# gloBrdB.net
KiCad netlist of a schematic drawn in EAGLE
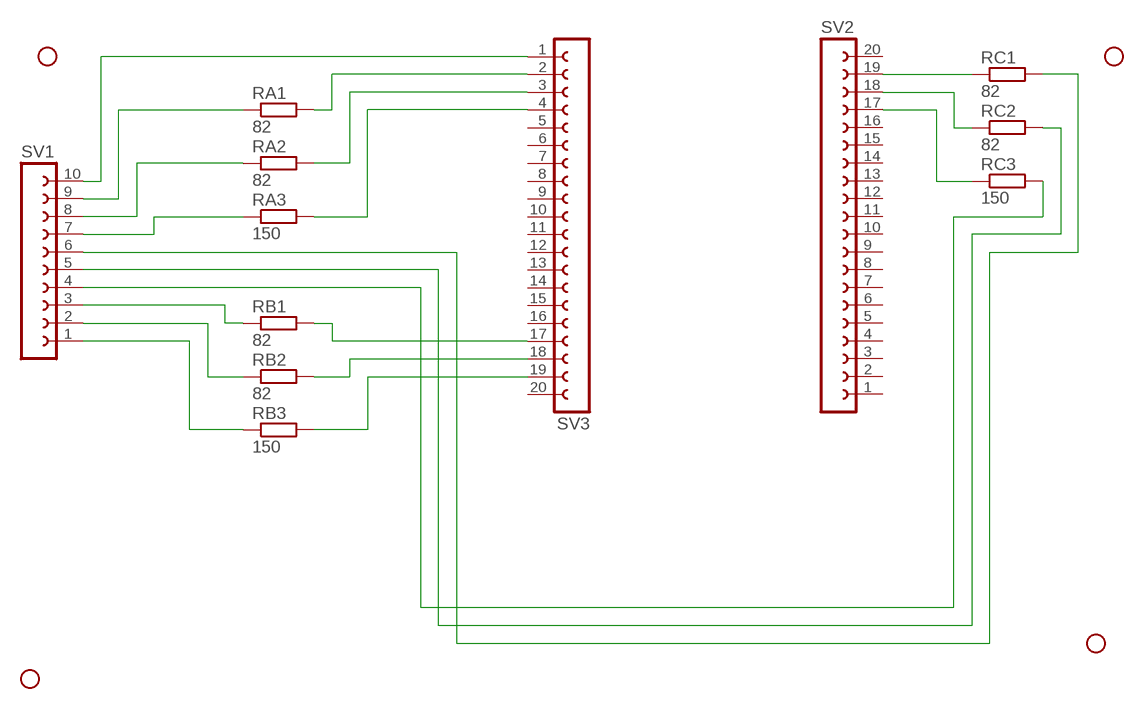
[diagram p0: schematic, sheet 1]

(export (version "E")
  (design (tool "Eeschema 10.0.6"))
  (components
    (comp (ref "RA1")
      (value "82")
      (footprint "eagle-import:0204_7")
      (libsource (lib "eagle-import") (part "R-EU_0204/7"))
    )
    (comp (ref "RA2")
      (value "82")
      (footprint "eagle-import:0204_7")
      (libsource (lib "eagle-import") (part "R-EU_0204/7"))
    )
    (comp (ref "RA3")
      (value "150")
      (footprint "eagle-import:0204_7")
      (libsource (lib "eagle-import") (part "R-EU_0204/7"))
    )
    (comp (ref "RB1")
      (value "82")
      (footprint "eagle-import:0204_7")
      (libsource (lib "eagle-import") (part "R-EU_0204/7"))
    )
    (comp (ref "RB2")
      (value "82")
      (footprint "eagle-import:0204_7")
      (libsource (lib "eagle-import") (part "R-EU_0204/7"))
    )
    (comp (ref "RB3")
      (value "150")
      (footprint "eagle-import:0204_7")
      (libsource (lib "eagle-import") (part "R-EU_0204/7"))
    )
    (comp (ref "RC1")
      (value "82")
      (footprint "eagle-import:0204_7")
      (libsource (lib "eagle-import") (part "R-EU_0204/7"))
    )
    (comp (ref "RC2")
      (value "82")
      (footprint "eagle-import:0204_7")
      (libsource (lib "eagle-import") (part "R-EU_0204/7"))
    )
    (comp (ref "RC3")
      (value "150")
      (footprint "eagle-import:0204_7")
      (libsource (lib "eagle-import") (part "R-EU_0204/7"))
    )
    (comp (ref "STANDOFF1")
      (value "STAND-OFF")
      (footprint "eagle-import:STAND-OFF")
      (libsource (lib "eagle-import") (part "STAND-OFF"))
    )
    (comp (ref "STANDOFF2")
      (value "STAND-OFF")
      (footprint "eagle-import:STAND-OFF")
      (libsource (lib "eagle-import") (part "STAND-OFF"))
    )
    (comp (ref "STANDOFF3")
      (value "STAND-OFF")
      (footprint "eagle-import:STAND-OFF")
      (libsource (lib "eagle-import") (part "STAND-OFF"))
    )
    (comp (ref "STANDOFF4")
      (value "STAND-OFF")
      (footprint "eagle-import:STAND-OFF")
      (libsource (lib "eagle-import") (part "STAND-OFF"))
    )
    (comp (ref "SV1")
      (value "FE10-1")
      (footprint "eagle-import:FE10")
      (libsource (lib "eagle-import") (part "FE10-1"))
    )
    (comp (ref "SV2")
      (value "FE20-1")
      (footprint "eagle-import:FE20")
      (libsource (lib "eagle-import") (part "FE20-1"))
    )
    (comp (ref "SV3")
      (value "FE20-1")
      (footprint "eagle-import:FE20")
      (libsource (lib "eagle-import") (part "FE20-1"))
    )
  )
  (nets
    (net (code "1") (name "Net-(RA1-Pad1)") (class "Default")
      (node (ref "RA1") (pin "1") (pinfunction "1_1") (pintype "passive"))
      (node (ref "SV1") (pin "9") (pinfunction "9_9") (pintype "passive"))
    )
    (net (code "2") (name "Net-(RA1-Pad2)") (class "Default")
      (node (ref "RA1") (pin "2") (pinfunction "2_2") (pintype "passive"))
      (node (ref "SV3") (pin "2") (pinfunction "2_2") (pintype "passive"))
    )
    (net (code "3") (name "Net-(RA2-Pad1)") (class "Default")
      (node (ref "RA2") (pin "1") (pinfunction "1_1") (pintype "passive"))
      (node (ref "SV1") (pin "8") (pinfunction "8_8") (pintype "passive"))
    )
    (net (code "4") (name "Net-(RA2-Pad2)") (class "Default")
      (node (ref "RA2") (pin "2") (pinfunction "2_2") (pintype "passive"))
      (node (ref "SV3") (pin "3") (pinfunction "3_3") (pintype "passive"))
    )
    (net (code "5") (name "Net-(RA3-Pad1)") (class "Default")
      (node (ref "RA3") (pin "1") (pinfunction "1_1") (pintype "passive"))
      (node (ref "SV1") (pin "7") (pinfunction "7_7") (pintype "passive"))
    )
    (net (code "6") (name "Net-(RA3-Pad2)") (class "Default")
      (node (ref "RA3") (pin "2") (pinfunction "2_2") (pintype "passive"))
      (node (ref "SV3") (pin "4") (pinfunction "4_4") (pintype "passive"))
    )
    (net (code "7") (name "Net-(RB1-Pad1)") (class "Default")
      (node (ref "RB1") (pin "1") (pinfunction "1_1") (pintype "passive"))
      (node (ref "SV1") (pin "3") (pinfunction "3_3") (pintype "passive"))
    )
    (net (code "8") (name "Net-(RB1-Pad2)") (class "Default")
      (node (ref "RB1") (pin "2") (pinfunction "2_2") (pintype "passive"))
      (node (ref "SV3") (pin "17") (pinfunction "17_17") (pintype "passive"))
    )
    (net (code "9") (name "Net-(RB2-Pad1)") (class "Default")
      (node (ref "RB2") (pin "1") (pinfunction "1_1") (pintype "passive"))
      (node (ref "SV1") (pin "2") (pinfunction "2_2") (pintype "passive"))
    )
    (net (code "10") (name "Net-(RB2-Pad2)") (class "Default")
      (node (ref "RB2") (pin "2") (pinfunction "2_2") (pintype "passive"))
      (node (ref "SV3") (pin "18") (pinfunction "18_18") (pintype "passive"))
    )
    (net (code "11") (name "Net-(RB3-Pad1)") (class "Default")
      (node (ref "RB3") (pin "1") (pinfunction "1_1") (pintype "passive"))
      (node (ref "SV1") (pin "1") (pinfunction "1_1") (pintype "passive"))
    )
    (net (code "12") (name "Net-(RB3-Pad2)") (class "Default")
      (node (ref "RB3") (pin "2") (pinfunction "2_2") (pintype "passive"))
      (node (ref "SV3") (pin "19") (pinfunction "19_19") (pintype "passive"))
    )
    (net (code "13") (name "Net-(RC1-Pad1)") (class "Default")
      (node (ref "RC1") (pin "1") (pinfunction "1_1") (pintype "passive"))
      (node (ref "SV2") (pin "19") (pinfunction "19_19") (pintype "passive"))
    )
    (net (code "14") (name "Net-(RC1-Pad2)") (class "Default")
      (node (ref "RC1") (pin "2") (pinfunction "2_2") (pintype "passive"))
      (node (ref "SV1") (pin "6") (pinfunction "6_6") (pintype "passive"))
    )
    (net (code "15") (name "Net-(RC2-Pad1)") (class "Default")
      (node (ref "RC2") (pin "1") (pinfunction "1_1") (pintype "passive"))
      (node (ref "SV2") (pin "18") (pinfunction "18_18") (pintype "passive"))
    )
    (net (code "16") (name "Net-(RC2-Pad2)") (class "Default")
      (node (ref "RC2") (pin "2") (pinfunction "2_2") (pintype "passive"))
      (node (ref "SV1") (pin "5") (pinfunction "5_5") (pintype "passive"))
    )
    (net (code "17") (name "Net-(RC3-Pad1)") (class "Default")
      (node (ref "RC3") (pin "1") (pinfunction "1_1") (pintype "passive"))
      (node (ref "SV2") (pin "17") (pinfunction "17_17") (pintype "passive"))
    )
    (net (code "18") (name "Net-(RC3-Pad2)") (class "Default")
      (node (ref "RC3") (pin "2") (pinfunction "2_2") (pintype "passive"))
      (node (ref "SV1") (pin "4") (pinfunction "4_4") (pintype "passive"))
    )
    (net (code "19") (name "Net-(SV1-Pad10)") (class "Default")
      (node (ref "SV1") (pin "10") (pinfunction "10_10") (pintype "passive"))
      (node (ref "SV3") (pin "1") (pinfunction "1_1") (pintype "passive"))
    )
    (net (code "20") (name "unconnected-(SV2-Pad1)") (class "Default")
      (node (ref "SV2") (pin "1") (pinfunction "1_1") (pintype "passive"))
    )
    (net (code "21") (name "unconnected-(SV2-Pad2)") (class "Default")
      (node (ref "SV2") (pin "2") (pinfunction "2_2") (pintype "passive"))
    )
    (net (code "22") (name "unconnected-(SV2-Pad3)") (class "Default")
      (node (ref "SV2") (pin "3") (pinfunction "3_3") (pintype "passive"))
    )
    (net (code "23") (name "unconnected-(SV2-Pad4)") (class "Default")
      (node (ref "SV2") (pin "4") (pinfunction "4_4") (pintype "passive"))
    )
    (net (code "24") (name "unconnected-(SV2-Pad5)") (class "Default")
      (node (ref "SV2") (pin "5") (pinfunction "5_5") (pintype "passive"))
    )
    (net (code "25") (name "unconnected-(SV2-Pad6)") (class "Default")
      (node (ref "SV2") (pin "6") (pinfunction "6_6") (pintype "passive"))
    )
    (net (code "26") (name "unconnected-(SV2-Pad7)") (class "Default")
      (node (ref "SV2") (pin "7") (pinfunction "7_7") (pintype "passive"))
    )
    (net (code "27") (name "unconnected-(SV2-Pad8)") (class "Default")
      (node (ref "SV2") (pin "8") (pinfunction "8_8") (pintype "passive"))
    )
    (net (code "28") (name "unconnected-(SV2-Pad9)") (class "Default")
      (node (ref "SV2") (pin "9") (pinfunction "9_9") (pintype "passive"))
    )
    (net (code "29") (name "unconnected-(SV2-Pad10)") (class "Default")
      (node (ref "SV2") (pin "10") (pinfunction "10_10") (pintype "passive"))
    )
    (net (code "30") (name "unconnected-(SV2-Pad11)") (class "Default")
      (node (ref "SV2") (pin "11") (pinfunction "11_11") (pintype "passive"))
    )
    (net (code "31") (name "unconnected-(SV2-Pad12)") (class "Default")
      (node (ref "SV2") (pin "12") (pinfunction "12_12") (pintype "passive"))
    )
    (net (code "32") (name "unconnected-(SV2-Pad13)") (class "Default")
      (node (ref "SV2") (pin "13") (pinfunction "13_13") (pintype "passive"))
    )
    (net (code "33") (name "unconnected-(SV2-Pad14)") (class "Default")
      (node (ref "SV2") (pin "14") (pinfunction "14_14") (pintype "passive"))
    )
    (net (code "34") (name "unconnected-(SV2-Pad15)") (class "Default")
      (node (ref "SV2") (pin "15") (pinfunction "15_15") (pintype "passive"))
    )
    (net (code "35") (name "unconnected-(SV2-Pad16)") (class "Default")
      (node (ref "SV2") (pin "16") (pinfunction "16_16") (pintype "passive"))
    )
    (net (code "36") (name "unconnected-(SV2-Pad20)") (class "Default")
      (node (ref "SV2") (pin "20") (pinfunction "20_20") (pintype "passive"))
    )
    (net (code "37") (name "unconnected-(SV3-Pad5)") (class "Default")
      (node (ref "SV3") (pin "5") (pinfunction "5_5") (pintype "passive"))
    )
    (net (code "38") (name "unconnected-(SV3-Pad6)") (class "Default")
      (node (ref "SV3") (pin "6") (pinfunction "6_6") (pintype "passive"))
    )
    (net (code "39") (name "unconnected-(SV3-Pad7)") (class "Default")
      (node (ref "SV3") (pin "7") (pinfunction "7_7") (pintype "passive"))
    )
    (net (code "40") (name "unconnected-(SV3-Pad8)") (class "Default")
      (node (ref "SV3") (pin "8") (pinfunction "8_8") (pintype "passive"))
    )
    (net (code "41") (name "unconnected-(SV3-Pad9)") (class "Default")
      (node (ref "SV3") (pin "9") (pinfunction "9_9") (pintype "passive"))
    )
    (net (code "42") (name "unconnected-(SV3-Pad10)") (class "Default")
      (node (ref "SV3") (pin "10") (pinfunction "10_10") (pintype "passive"))
    )
    (net (code "43") (name "unconnected-(SV3-Pad11)") (class "Default")
      (node (ref "SV3") (pin "11") (pinfunction "11_11") (pintype "passive"))
    )
    (net (code "44") (name "unconnected-(SV3-Pad12)") (class "Default")
      (node (ref "SV3") (pin "12") (pinfunction "12_12") (pintype "passive"))
    )
    (net (code "45") (name "unconnected-(SV3-Pad13)") (class "Default")
      (node (ref "SV3") (pin "13") (pinfunction "13_13") (pintype "passive"))
    )
    (net (code "46") (name "unconnected-(SV3-Pad14)") (class "Default")
      (node (ref "SV3") (pin "14") (pinfunction "14_14") (pintype "passive"))
    )
    (net (code "47") (name "unconnected-(SV3-Pad15)") (class "Default")
      (node (ref "SV3") (pin "15") (pinfunction "15_15") (pintype "passive"))
    )
    (net (code "48") (name "unconnected-(SV3-Pad16)") (class "Default")
      (node (ref "SV3") (pin "16") (pinfunction "16_16") (pintype "passive"))
    )
    (net (code "49") (name "unconnected-(SV3-Pad20)") (class "Default")
      (node (ref "SV3") (pin "20") (pinfunction "20_20") (pintype "passive"))
    )
  )
)
